# 10-Sensing.net
KiCad netlist of a schematic drawn in Altium Designer
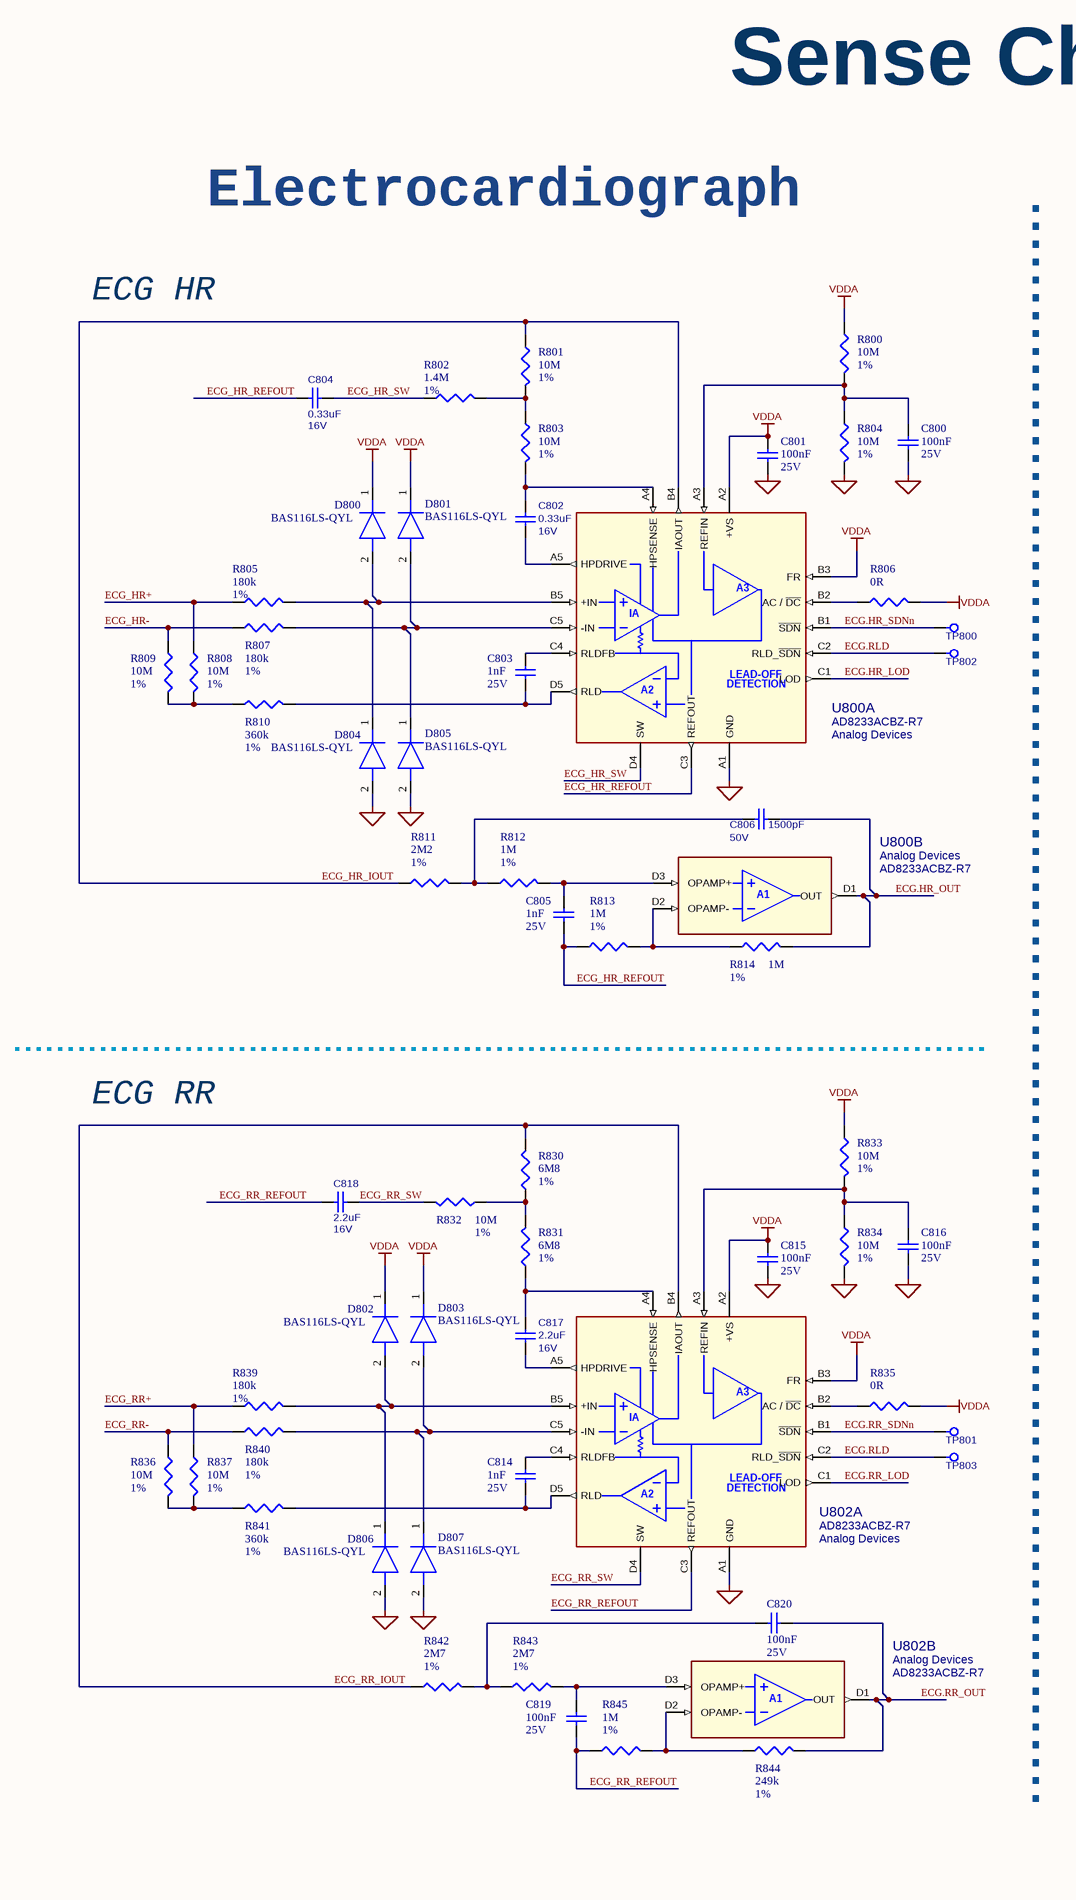
[diagram p0: 10-Sensing.SchDoc, left]
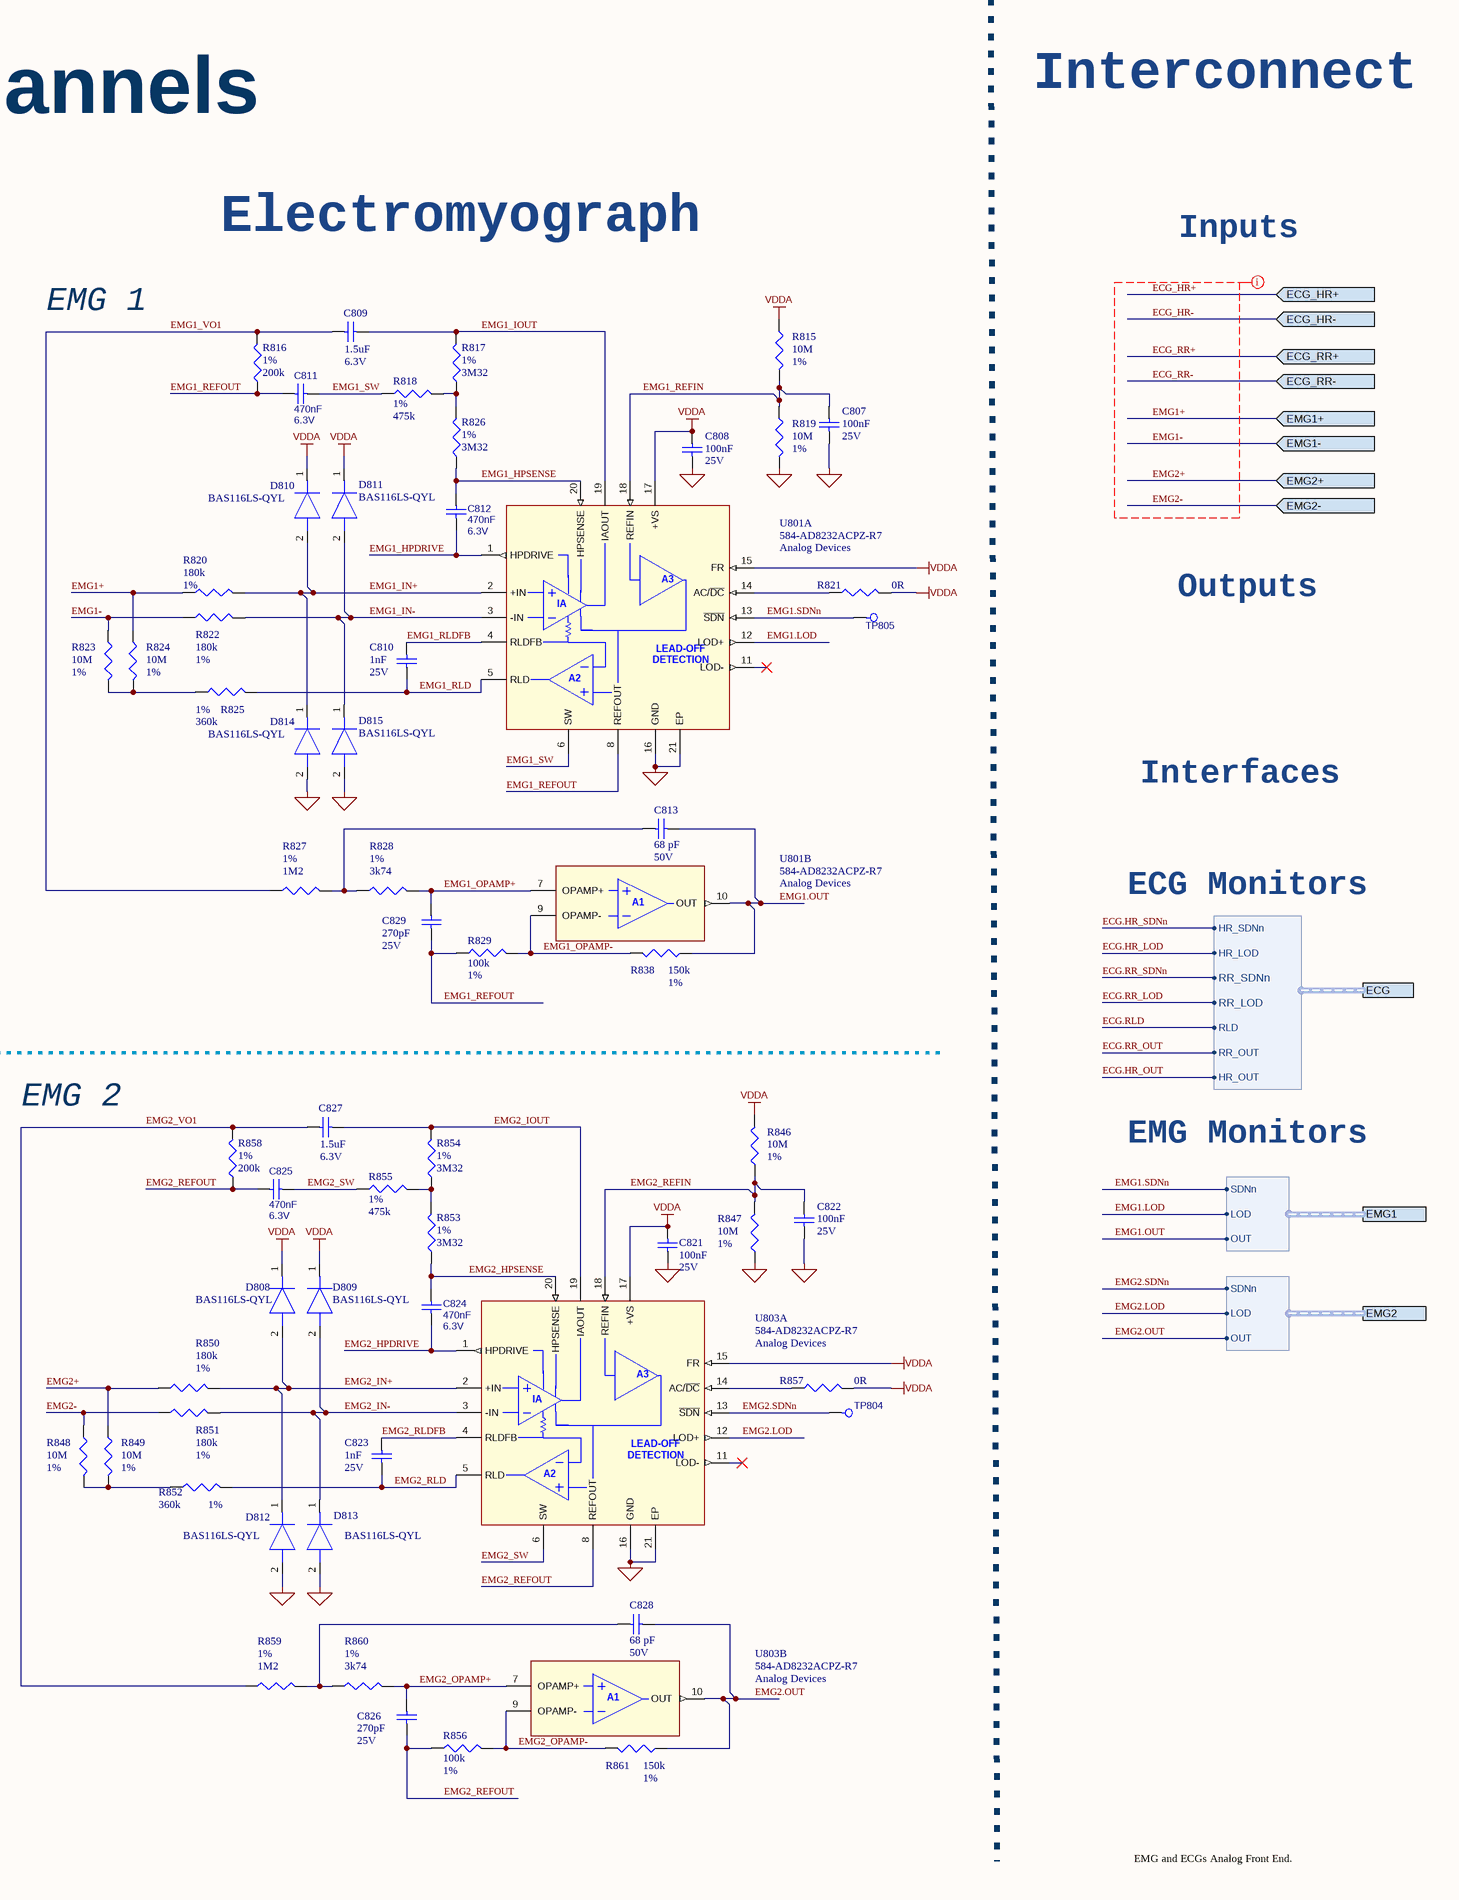
[diagram p1: 10-Sensing.SchDoc, right]

(export (version "E")
  (design (tool "Eeschema 10.0.6"))
  (components
    (comp (ref "C800")
      (value "100nF")
      (footprint "C0201_C")
      (fields
        (field (name "MANUFACTURER") "Murata")
        (field (name "MANUFACTURER PART NUMBER") "GRM033R61E104KE14J")
        (field (name "RATED DC VOLTAGE (URDC)") "25V")
      )
      (libsource (lib "MP-LIBRARY") (part "GRM033R61E104KE14J"))
    )
    (comp (ref "C801")
      (value "100nF")
      (footprint "C0201_C")
      (fields
        (field (name "MANUFACTURER") "Murata")
        (field (name "MANUFACTURER PART NUMBER") "GRM033R61E104KE14J")
        (field (name "RATED DC VOLTAGE (URDC)") "25V")
      )
      (libsource (lib "MP-LIBRARY") (part "GRM033R61E104KE14J"))
    )
    (comp (ref "C802")
      (value "0.33uF")
      (footprint "CAP0402_REDUCED")
      (description "Capacitor, 0.33uF, X7S, 16V, 10%, 0402")
      (fields
        (field (name "MANUFACTURER") "TDK")
        (field (name "RATING") "16V")
        (field (name "MANUFACTURER PART NUMBER") "CGA2B1X7S1C334K050BC")
      )
      (libsource (lib "MP-LIBRARY") (part "CGA2B1X7S1C334K050BC"))
    )
    (comp (ref "C803")
      (value "1nF")
      (footprint "C0201_C")
      (fields
        (field (name "MANUFACTURER") "Murata")
        (field (name "MANUFACTURER PART NUMBER") "GRM033R71E102KA01J")
        (field (name "RATED DC VOLTAGE (URDC)") "25V")
      )
      (libsource (lib "MP-LIBRARY") (part "GRM033R71E102KA01J"))
    )
    (comp (ref "C804")
      (value "0.33uF")
      (footprint "CAP0402_REDUCED")
      (description "Capacitor, 0.33uF, X7S, 16V, 10%, 0402")
      (fields
        (field (name "MANUFACTURER") "TDK")
        (field (name "RATING") "16V")
        (field (name "MANUFACTURER PART NUMBER") "CGA2B1X7S1C334K050BC")
      )
      (libsource (lib "MP-LIBRARY") (part "CGA2B1X7S1C334K050BC"))
    )
    (comp (ref "C805")
      (value "1nF")
      (footprint "C0201_C")
      (fields
        (field (name "MANUFACTURER") "Murata")
        (field (name "MANUFACTURER PART NUMBER") "GRM033R71E102KA01J")
        (field (name "RATED DC VOLTAGE (URDC)") "25V")
      )
      (libsource (lib "MP-LIBRARY") (part "GRM033R71E102KA01J"))
    )
    (comp (ref "C806")
      (value "1500pF")
      (footprint "CAP0402_REDUCED")
      (description "Capacitor, 1500pF, X7R, 50V, 10%, 0402")
      (fields
        (field (name "MANUFACTURER") "Murata")
        (field (name "RATING") "50V")
        (field (name "MANUFACTURER PART NUMBER") "GCM155R71H152KA37D")
      )
      (libsource (lib "MP-LIBRARY") (part "GCM155R71H152KA37D"))
    )
    (comp (ref "C807")
      (value "100nF")
      (footprint "C0201_C")
      (fields
        (field (name "MANUFACTURER") "Murata")
        (field (name "MANUFACTURER PART NUMBER") "GRM033R61E104KE14J")
        (field (name "RATED DC VOLTAGE (URDC)") "25V")
      )
      (libsource (lib "MP-LIBRARY") (part "GRM033R61E104KE14J"))
    )
    (comp (ref "C808")
      (value "100nF")
      (footprint "C0201_C")
      (fields
        (field (name "MANUFACTURER") "Murata")
        (field (name "MANUFACTURER PART NUMBER") "GRM033R61E104KE14J")
        (field (name "RATED DC VOLTAGE (URDC)") "25V")
      )
      (libsource (lib "MP-LIBRARY") (part "GRM033R61E104KE14J"))
    )
    (comp (ref "C809")
      (value "1.5uF")
      (footprint "C0201_C")
      (fields
        (field (name "MANUFACTURER") "Murata")
        (field (name "MANUFACTURER PART NUMBER") "GRM033R60J155ME14D")
        (field (name "RATED DC VOLTAGE (URDC)") "6.3V")
      )
      (libsource (lib "MP-LIBRARY") (part "GRM033R60J155ME14D"))
    )
    (comp (ref "C810")
      (value "1nF")
      (footprint "C0201_C")
      (fields
        (field (name "MANUFACTURER") "Murata")
        (field (name "MANUFACTURER PART NUMBER") "GRM033R71E102KA01J")
        (field (name "RATED DC VOLTAGE (URDC)") "25V")
      )
      (libsource (lib "MP-LIBRARY") (part "GRM033R71E102KA01J"))
    )
    (comp (ref "C811")
      (value "470nF")
      (footprint "C0201_C")
      (description "Capacitor, 470nF, X5R, 6.3V, 10%, 0201, Implant Grade")
      (fields
        (field (name "MANUFACTURER") "Murata")
        (field (name "MANUFACTURER PART NUMBER") "GRT033R60J474KE01D")
        (field (name "RATING") "6.3V")
      )
      (libsource (lib "MP-LIBRARY") (part "GRT033R60J474KE01D"))
    )
    (comp (ref "C812")
      (value "470nF")
      (footprint "C0201_C")
      (description "Capacitor, 470nF, X5R, 6.3V, 10%, 0201, Implant Grade")
      (fields
        (field (name "MANUFACTURER") "Murata")
        (field (name "MANUFACTURER PART NUMBER") "GRT033R60J474KE01D")
        (field (name "RATING") "6.3V")
      )
      (libsource (lib "MP-LIBRARY") (part "GRT033R60J474KE01D"))
    )
    (comp (ref "C813")
      (value "68 pF")
      (footprint "C0201_C")
      (description "68 pF ±5% 50V Ceramic Capacitor C0G, NP0 0201 (0603 Metric)")
      (fields
        (field (name "MANUFACTURER") "Murata Electronics")
        (field (name "MANUFACTURER PART NUMBER") "GRM0335C1H680JA01D")
        (field (name "RATED DC VOLTAGE (URDC)") "50V")
      )
      (libsource (lib "MP-LIBRARY") (part "GRM0335C1H680JA01D"))
    )
    (comp (ref "C814")
      (value "1nF")
      (footprint "C0201_C")
      (fields
        (field (name "MANUFACTURER") "Murata")
        (field (name "MANUFACTURER PART NUMBER") "GRM033R71E102KA01J")
        (field (name "RATED DC VOLTAGE (URDC)") "25V")
      )
      (libsource (lib "MP-LIBRARY") (part "GRM033R71E102KA01J"))
    )
    (comp (ref "C815")
      (value "100nF")
      (footprint "C0201_C")
      (fields
        (field (name "MANUFACTURER") "Murata")
        (field (name "MANUFACTURER PART NUMBER") "GRM033R61E104KE14J")
        (field (name "RATED DC VOLTAGE (URDC)") "25V")
      )
      (libsource (lib "MP-LIBRARY") (part "GRM033R61E104KE14J"))
    )
    (comp (ref "C816")
      (value "100nF")
      (footprint "C0201_C")
      (fields
        (field (name "MANUFACTURER") "Murata")
        (field (name "MANUFACTURER PART NUMBER") "GRM033R61E104KE14J")
        (field (name "RATED DC VOLTAGE (URDC)") "25V")
      )
      (libsource (lib "MP-LIBRARY") (part "GRM033R61E104KE14J"))
    )
    (comp (ref "C817")
      (value "2.2uF")
      (footprint "CAP0603_REDUCED")
      (description "Capacitor, 2.2uF, X7R, 16V, 10%, 0603, Implant-grade")
      (fields
        (field (name "MANUFACTURER") "Murata")
        (field (name "RATING") "16V")
        (field (name "MANUFACTURER PART NUMBER") "GRM188Z71C225ME43J")
      )
      (libsource (lib "MP-LIBRARY") (part "GRM188Z71C225ME43J"))
    )
    (comp (ref "C818")
      (value "2.2uF")
      (footprint "CAP0603_REDUCED")
      (description "Capacitor, 2.2uF, X7R, 16V, 10%, 0603, Implant-grade")
      (fields
        (field (name "MANUFACTURER") "Murata")
        (field (name "RATING") "16V")
        (field (name "MANUFACTURER PART NUMBER") "GRM188Z71C225ME43J")
      )
      (libsource (lib "MP-LIBRARY") (part "GRM188Z71C225ME43J"))
    )
    (comp (ref "C819")
      (value "100nF")
      (footprint "C0201_C")
      (fields
        (field (name "MANUFACTURER") "Murata")
        (field (name "MANUFACTURER PART NUMBER") "GRM033R61E104KE14J")
        (field (name "RATED DC VOLTAGE (URDC)") "25V")
      )
      (libsource (lib "MP-LIBRARY") (part "GRM033R61E104KE14J"))
    )
    (comp (ref "C820")
      (value "100nF")
      (footprint "C0201_C")
      (fields
        (field (name "MANUFACTURER") "Murata")
        (field (name "MANUFACTURER PART NUMBER") "GRM033R61E104KE14J")
        (field (name "RATED DC VOLTAGE (URDC)") "25V")
      )
      (libsource (lib "MP-LIBRARY") (part "GRM033R61E104KE14J"))
    )
    (comp (ref "C821")
      (value "100nF")
      (footprint "C0201_C")
      (fields
        (field (name "MANUFACTURER") "Murata")
        (field (name "MANUFACTURER PART NUMBER") "GRM033R61E104KE14J")
        (field (name "RATED DC VOLTAGE (URDC)") "25V")
      )
      (libsource (lib "MP-LIBRARY") (part "GRM033R61E104KE14J"))
    )
    (comp (ref "C822")
      (value "100nF")
      (footprint "C0201_C")
      (fields
        (field (name "MANUFACTURER") "Murata")
        (field (name "MANUFACTURER PART NUMBER") "GRM033R61E104KE14J")
        (field (name "RATED DC VOLTAGE (URDC)") "25V")
      )
      (libsource (lib "MP-LIBRARY") (part "GRM033R61E104KE14J"))
    )
    (comp (ref "C823")
      (value "1nF")
      (footprint "C0201_C")
      (fields
        (field (name "MANUFACTURER") "Murata")
        (field (name "MANUFACTURER PART NUMBER") "GRM033R71E102KA01J")
        (field (name "RATED DC VOLTAGE (URDC)") "25V")
      )
      (libsource (lib "MP-LIBRARY") (part "GRM033R71E102KA01J"))
    )
    (comp (ref "C824")
      (value "470nF")
      (footprint "C0201_C")
      (description "Capacitor, 470nF, X5R, 6.3V, 10%, 0201, Implant Grade")
      (fields
        (field (name "MANUFACTURER") "Murata")
        (field (name "MANUFACTURER PART NUMBER") "GRT033R60J474KE01D")
        (field (name "RATING") "6.3V")
      )
      (libsource (lib "MP-LIBRARY") (part "GRT033R60J474KE01D"))
    )
    (comp (ref "C825")
      (value "470nF")
      (footprint "C0201_C")
      (description "Capacitor, 470nF, X5R, 6.3V, 10%, 0201, Implant Grade")
      (fields
        (field (name "MANUFACTURER") "Murata")
        (field (name "MANUFACTURER PART NUMBER") "GRT033R60J474KE01D")
        (field (name "RATING") "6.3V")
      )
      (libsource (lib "MP-LIBRARY") (part "GRT033R60J474KE01D"))
    )
    (comp (ref "C826")
      (value "270pF")
      (footprint "C0201_C")
      (description "270 pF ±5% 25V Ceramic Capacitor C0G, NP0 0201 (0603 Metric)")
      (fields
        (field (name "MANUFACTURER") "Murata Electronics")
        (field (name "MANUFACTURER PART NUMBER") "GRM0335C1E271JA01D")
        (field (name "RATED DC VOLTAGE (URDC)") "25V")
      )
      (libsource (lib "MP-LIBRARY") (part "GRM0335C1E271JA01D"))
    )
    (comp (ref "C827")
      (value "1.5uF")
      (footprint "C0201_C")
      (fields
        (field (name "MANUFACTURER") "Murata")
        (field (name "MANUFACTURER PART NUMBER") "GRM033R60J155ME14D")
        (field (name "RATED DC VOLTAGE (URDC)") "6.3V")
      )
      (libsource (lib "MP-LIBRARY") (part "GRM033R60J155ME14D"))
    )
    (comp (ref "C828")
      (value "68 pF")
      (footprint "C0201_C")
      (description "68 pF ±5% 50V Ceramic Capacitor C0G, NP0 0201 (0603 Metric)")
      (fields
        (field (name "MANUFACTURER") "Murata Electronics")
        (field (name "MANUFACTURER PART NUMBER") "GRM0335C1H680JA01D")
        (field (name "RATED DC VOLTAGE (URDC)") "50V")
      )
      (libsource (lib "MP-LIBRARY") (part "GRM0335C1H680JA01D"))
    )
    (comp (ref "C829")
      (value "270pF")
      (footprint "C0201_C")
      (description "270 pF ±5% 25V Ceramic Capacitor C0G, NP0 0201 (0603 Metric)")
      (fields
        (field (name "MANUFACTURER") "Murata Electronics")
        (field (name "MANUFACTURER PART NUMBER") "GRM0335C1E271JA01D")
        (field (name "RATED DC VOLTAGE (URDC)") "25V")
      )
      (libsource (lib "MP-LIBRARY") (part "GRM0335C1E271JA01D"))
    )
    (comp (ref "D800")
      (value "BAS116LS-QYL")
      (footprint "BAS116LSQYL")
      (description "Diode")
      (fields (field (name "MOUSER PART NUMBER") "771-BAS116LS-QYL") (field (name "MANUFACTURER") "Nexperia"))
      (libsource (lib "MP-LIBRARY") (part "BAS116LS-QYL"))
    )
    (comp (ref "D801")
      (value "BAS116LS-QYL")
      (footprint "BAS116LSQYL")
      (description "Diode")
      (fields (field (name "MOUSER PART NUMBER") "771-BAS116LS-QYL") (field (name "MANUFACTURER") "Nexperia"))
      (libsource (lib "MP-LIBRARY") (part "BAS116LS-QYL"))
    )
    (comp (ref "D802")
      (value "BAS116LS-QYL")
      (footprint "BAS116LSQYL")
      (description "Diode")
      (fields (field (name "MOUSER PART NUMBER") "771-BAS116LS-QYL") (field (name "MANUFACTURER") "Nexperia"))
      (libsource (lib "MP-LIBRARY") (part "BAS116LS-QYL"))
    )
    (comp (ref "D803")
      (value "BAS116LS-QYL")
      (footprint "BAS116LSQYL")
      (description "Diode")
      (fields (field (name "MOUSER PART NUMBER") "771-BAS116LS-QYL") (field (name "MANUFACTURER") "Nexperia"))
      (libsource (lib "MP-LIBRARY") (part "BAS116LS-QYL"))
    )
    (comp (ref "D804")
      (value "BAS116LS-QYL")
      (footprint "BAS116LSQYL")
      (description "Diode")
      (fields (field (name "MOUSER PART NUMBER") "771-BAS116LS-QYL") (field (name "MANUFACTURER") "Nexperia"))
      (libsource (lib "MP-LIBRARY") (part "BAS116LS-QYL"))
    )
    (comp (ref "D805")
      (value "BAS116LS-QYL")
      (footprint "BAS116LSQYL")
      (description "Diode")
      (fields (field (name "MOUSER PART NUMBER") "771-BAS116LS-QYL") (field (name "MANUFACTURER") "Nexperia"))
      (libsource (lib "MP-LIBRARY") (part "BAS116LS-QYL"))
    )
    (comp (ref "D806")
      (value "BAS116LS-QYL")
      (footprint "BAS116LSQYL")
      (description "Diode")
      (fields (field (name "MOUSER PART NUMBER") "771-BAS116LS-QYL") (field (name "MANUFACTURER") "Nexperia"))
      (libsource (lib "MP-LIBRARY") (part "BAS116LS-QYL"))
    )
    (comp (ref "D807")
      (value "BAS116LS-QYL")
      (footprint "BAS116LSQYL")
      (description "Diode")
      (fields (field (name "MOUSER PART NUMBER") "771-BAS116LS-QYL") (field (name "MANUFACTURER") "Nexperia"))
      (libsource (lib "MP-LIBRARY") (part "BAS116LS-QYL"))
    )
    (comp (ref "D808")
      (value "BAS116LS-QYL")
      (footprint "BAS116LSQYL")
      (description "Diode")
      (fields (field (name "MOUSER PART NUMBER") "771-BAS116LS-QYL") (field (name "MANUFACTURER") "Nexperia"))
      (libsource (lib "MP-LIBRARY") (part "BAS116LS-QYL"))
    )
    (comp (ref "D809")
      (value "BAS116LS-QYL")
      (footprint "BAS116LSQYL")
      (description "Diode")
      (fields (field (name "MOUSER PART NUMBER") "771-BAS116LS-QYL") (field (name "MANUFACTURER") "Nexperia"))
      (libsource (lib "MP-LIBRARY") (part "BAS116LS-QYL"))
    )
    (comp (ref "D810")
      (value "BAS116LS-QYL")
      (footprint "BAS116LSQYL")
      (description "Diode")
      (fields (field (name "MOUSER PART NUMBER") "771-BAS116LS-QYL") (field (name "MANUFACTURER") "Nexperia"))
      (libsource (lib "MP-LIBRARY") (part "BAS116LS-QYL"))
    )
    (comp (ref "D811")
      (value "BAS116LS-QYL")
      (footprint "BAS116LSQYL")
      (description "Diode")
      (fields (field (name "MOUSER PART NUMBER") "771-BAS116LS-QYL") (field (name "MANUFACTURER") "Nexperia"))
      (libsource (lib "MP-LIBRARY") (part "BAS116LS-QYL"))
    )
    (comp (ref "D812")
      (value "BAS116LS-QYL")
      (footprint "BAS116LSQYL")
      (description "Diode")
      (fields (field (name "MOUSER PART NUMBER") "771-BAS116LS-QYL") (field (name "MANUFACTURER") "Nexperia"))
      (libsource (lib "MP-LIBRARY") (part "BAS116LS-QYL"))
    )
    (comp (ref "D813")
      (value "BAS116LS-QYL")
      (footprint "BAS116LSQYL")
      (description "Diode")
      (fields (field (name "MOUSER PART NUMBER") "771-BAS116LS-QYL") (field (name "MANUFACTURER") "Nexperia"))
      (libsource (lib "MP-LIBRARY") (part "BAS116LS-QYL"))
    )
    (comp (ref "D814")
      (value "BAS116LS-QYL")
      (footprint "BAS116LSQYL")
      (description "Diode")
      (fields (field (name "MOUSER PART NUMBER") "771-BAS116LS-QYL") (field (name "MANUFACTURER") "Nexperia"))
      (libsource (lib "MP-LIBRARY") (part "BAS116LS-QYL"))
    )
    (comp (ref "D815")
      (value "BAS116LS-QYL")
      (footprint "BAS116LSQYL")
      (description "Diode")
      (fields (field (name "MOUSER PART NUMBER") "771-BAS116LS-QYL") (field (name "MANUFACTURER") "Nexperia"))
      (libsource (lib "MP-LIBRARY") (part "BAS116LS-QYL"))
    )
    (comp (ref "R800")
      (value "10M")
      (footprint "R0201_C")
      (fields
        (field (name "MANUFACTURER") "Vishay Draloric")
        (field (name "MANUFACTURER PART NUMBER") "CRCW020110M0FNED")
        (field (name "TOLERANCE") "1%")
        (field (name "POWER") "50mW")
      )
      (libsource (lib "MP-LIBRARY") (part "CRCW020110M0FNED"))
    )
    (comp (ref "R801")
      (value "10M")
      (footprint "R0201_C")
      (fields
        (field (name "MANUFACTURER") "Vishay Draloric")
        (field (name "MANUFACTURER PART NUMBER") "CRCW020110M0FNED")
        (field (name "TOLERANCE") "1%")
        (field (name "POWER") "50mW")
      )
      (libsource (lib "MP-LIBRARY") (part "CRCW020110M0FNED"))
    )
    (comp (ref "R802")
      (value "1.4M")
      (footprint "R0201_C")
      (fields
        (field (name "MANUFACTURER") "Vishay Draloric")
        (field (name "MANUFACTURER PART NUMBER") "CRCW02011M40FNED")
        (field (name "TOLERANCE") "1%")
        (field (name "POWER") "50mW")
      )
      (libsource (lib "MP-LIBRARY") (part "CRCW02011M40FNED"))
    )
    (comp (ref "R803")
      (value "10M")
      (footprint "R0201_C")
      (fields
        (field (name "MANUFACTURER") "Vishay Draloric")
        (field (name "MANUFACTURER PART NUMBER") "CRCW020110M0FNED")
        (field (name "TOLERANCE") "1%")
        (field (name "POWER") "50mW")
      )
      (libsource (lib "MP-LIBRARY") (part "CRCW020110M0FNED"))
    )
    (comp (ref "R804")
      (value "10M")
      (footprint "R0201_C")
      (fields
        (field (name "MANUFACTURER") "Vishay Draloric")
        (field (name "MANUFACTURER PART NUMBER") "CRCW020110M0FNED")
        (field (name "TOLERANCE") "1%")
        (field (name "POWER") "50mW")
      )
      (libsource (lib "MP-LIBRARY") (part "CRCW020110M0FNED"))
    )
    (comp (ref "R805")
      (value "180k")
      (footprint "R0201_C")
      (fields
        (field (name "MANUFACTURER") "Vishay")
        (field (name "MANUFACTURER PART NUMBER") "CRCW0201180KFNED")
        (field (name "TOLERANCE") "1%")
        (field (name "POWER") "50mW")
      )
      (libsource (lib "MP-LIBRARY") (part "CRCW0201180KFNED"))
    )
    (comp (ref "R806")
      (value "0R")
      (footprint "R0201_C")
      (description "Fixed Resistor, Metal Glaze/thick Film, 0.05W, 0ohm, Surface Mount, 0201")
      (fields
        (field (name "MANUFACTURER") "Vishay")
        (field (name "MANUFACTURER PART NUMBER") "CRCW02010000Z0ED")
      )
      (libsource (lib "MP-LIBRARY") (part "CRCW02010000Z0ED"))
    )
    (comp (ref "R807")
      (value "180k")
      (footprint "R0201_C")
      (fields
        (field (name "MANUFACTURER") "Vishay")
        (field (name "MANUFACTURER PART NUMBER") "CRCW0201180KFNED")
        (field (name "TOLERANCE") "1%")
        (field (name "POWER") "50mW")
      )
      (libsource (lib "MP-LIBRARY") (part "CRCW0201180KFNED"))
    )
    (comp (ref "R808")
      (value "10M")
      (footprint "R0201_C")
      (fields
        (field (name "MANUFACTURER") "Vishay Draloric")
        (field (name "MANUFACTURER PART NUMBER") "CRCW020110M0FNED")
        (field (name "TOLERANCE") "1%")
        (field (name "POWER") "50mW")
      )
      (libsource (lib "MP-LIBRARY") (part "CRCW020110M0FNED"))
    )
    (comp (ref "R809")
      (value "10M")
      (footprint "R0201_C")
      (fields
        (field (name "MANUFACTURER") "Vishay Draloric")
        (field (name "MANUFACTURER PART NUMBER") "CRCW020110M0FNED")
        (field (name "TOLERANCE") "1%")
        (field (name "POWER") "50mW")
      )
      (libsource (lib "MP-LIBRARY") (part "CRCW020110M0FNED"))
    )
    (comp (ref "R810")
      (value "360k")
      (footprint "R0201_C")
      (fields
        (field (name "MANUFACTURER") "Vishay")
        (field (name "MANUFACTURER PART NUMBER") "CRCW0201360KFNED")
        (field (name "TOLERANCE") "1%")
        (field (name "POWER") "50mW")
      )
      (libsource (lib "MP-LIBRARY") (part "CRCW0201360KFNED"))
    )
    (comp (ref "R811")
      (value "2M2")
      (footprint "R0201_C")
      (fields
        (field (name "MANUFACTURER") "Vishay Draloric")
        (field (name "MANUFACTURER PART NUMBER") "CRCW02012M20FNED")
        (field (name "TOLERANCE") "1%")
        (field (name "POWER") "50mW")
      )
      (libsource (lib "MP-LIBRARY") (part "CRCW02012M20FNED"))
    )
    (comp (ref "R812")
      (value "1M")
      (footprint "R0201_C")
      (fields
        (field (name "MANUFACTURER") "Vishay")
        (field (name "MANUFACTURER PART NUMBER") "CRCW02011M00FNED")
        (field (name "TOLERANCE") "1%")
        (field (name "POWER") "50mW")
      )
      (libsource (lib "MP-LIBRARY") (part "CRCW02011M00FNED"))
    )
    (comp (ref "R813")
      (value "1M")
      (footprint "R0201_C")
      (fields
        (field (name "MANUFACTURER") "Vishay")
        (field (name "MANUFACTURER PART NUMBER") "CRCW02011M00FNED")
        (field (name "TOLERANCE") "1%")
        (field (name "POWER") "50mW")
      )
      (libsource (lib "MP-LIBRARY") (part "CRCW02011M00FNED"))
    )
    (comp (ref "R814")
      (value "1M")
      (footprint "R0201_C")
      (fields
        (field (name "MANUFACTURER") "Vishay")
        (field (name "MANUFACTURER PART NUMBER") "CRCW02011M00FNED")
        (field (name "TOLERANCE") "1%")
        (field (name "POWER") "50mW")
      )
      (libsource (lib "MP-LIBRARY") (part "CRCW02011M00FNED"))
    )
    (comp (ref "R815")
      (value "10M")
      (footprint "R0201_C")
      (fields
        (field (name "MANUFACTURER") "Vishay Draloric")
        (field (name "MANUFACTURER PART NUMBER") "CRCW020110M0FNED")
        (field (name "TOLERANCE") "1%")
        (field (name "POWER") "50mW")
      )
      (libsource (lib "MP-LIBRARY") (part "CRCW020110M0FNED"))
    )
    (comp (ref "R816")
      (value "200k")
      (footprint "R0201_C")
      (fields
        (field (name "MANUFACTURER") "Vishay")
        (field (name "MANUFACTURER PART NUMBER") "CRCW0201200KFNED")
        (field (name "TOLERANCE") "1%")
        (field (name "POWER") "50mW")
      )
      (libsource (lib "MP-LIBRARY") (part "CRCW0201200KFNED"))
    )
    (comp (ref "R817")
      (value "3M32")
      (footprint "R0201_C")
      (description "3.32 MOhms ±1% 0.05W, 1/20W Chip Resistor 0201 (0603 Metric) Thick Film")
      (fields
        (field (name "MANUFACTURER") "Vishay Dale")
        (field (name "MANUFACTURER PART NUMBER") "CRCW02013M32FNED")
        (field (name "TOLERANCE") "1%")
      )
      (libsource (lib "MP-LIBRARY") (part "CRCW02013M32FNED"))
    )
    (comp (ref "R818")
      (value "475k")
      (footprint "R0201_C")
      (description "475 kOhms ±1% 0.05W, 1/20W Chip Resistor 0201 (0603 Metric) Thick Film")
      (fields
        (field (name "MANUFACTURER") "Vishay Dale")
        (field (name "MANUFACTURER PART NUMBER") "CRCW0201475KFNED")
        (field (name "TOLERANCE") "1%")
      )
      (libsource (lib "MP-LIBRARY") (part "CRCW0201475KFNED"))
    )
    (comp (ref "R819")
      (value "10M")
      (footprint "R0201_C")
      (fields
        (field (name "MANUFACTURER") "Vishay Draloric")
        (field (name "MANUFACTURER PART NUMBER") "CRCW020110M0FNED")
        (field (name "TOLERANCE") "1%")
        (field (name "POWER") "50mW")
      )
      (libsource (lib "MP-LIBRARY") (part "CRCW020110M0FNED"))
    )
    (comp (ref "R820")
      (value "180k")
      (footprint "R0201_C")
      (fields
        (field (name "MANUFACTURER") "Vishay")
        (field (name "MANUFACTURER PART NUMBER") "CRCW0201180KFNED")
        (field (name "TOLERANCE") "1%")
        (field (name "POWER") "50mW")
      )
      (libsource (lib "MP-LIBRARY") (part "CRCW0201180KFNED"))
    )
    (comp (ref "R821")
      (value "0R")
      (footprint "R0201_C")
      (description "Fixed Resistor, Metal Glaze/thick Film, 0.05W, 0ohm, Surface Mount, 0201")
      (fields
        (field (name "MANUFACTURER") "Vishay")
        (field (name "MANUFACTURER PART NUMBER") "CRCW02010000Z0ED")
      )
      (libsource (lib "MP-LIBRARY") (part "CRCW02010000Z0ED"))
    )
    (comp (ref "R822")
      (value "180k")
      (footprint "R0201_C")
      (fields
        (field (name "MANUFACTURER") "Vishay")
        (field (name "MANUFACTURER PART NUMBER") "CRCW0201180KFNED")
        (field (name "TOLERANCE") "1%")
        (field (name "POWER") "50mW")
      )
      (libsource (lib "MP-LIBRARY") (part "CRCW0201180KFNED"))
    )
    (comp (ref "R823")
      (value "10M")
      (footprint "R0201_C")
      (fields
        (field (name "MANUFACTURER") "Vishay Draloric")
        (field (name "MANUFACTURER PART NUMBER") "CRCW020110M0FNED")
        (field (name "TOLERANCE") "1%")
        (field (name "POWER") "50mW")
      )
      (libsource (lib "MP-LIBRARY") (part "CRCW020110M0FNED"))
    )
    (comp (ref "R824")
      (value "10M")
      (footprint "R0201_C")
      (fields
        (field (name "MANUFACTURER") "Vishay Draloric")
        (field (name "MANUFACTURER PART NUMBER") "CRCW020110M0FNED")
        (field (name "TOLERANCE") "1%")
        (field (name "POWER") "50mW")
      )
      (libsource (lib "MP-LIBRARY") (part "CRCW020110M0FNED"))
    )
    (comp (ref "R825")
      (value "360k")
      (footprint "R0201_C")
      (fields
        (field (name "MANUFACTURER") "Vishay")
        (field (name "MANUFACTURER PART NUMBER") "CRCW0201360KFNED")
        (field (name "TOLERANCE") "1%")
        (field (name "POWER") "50mW")
      )
      (libsource (lib "MP-LIBRARY") (part "CRCW0201360KFNED"))
    )
    (comp (ref "R826")
      (value "3M32")
      (footprint "R0201_C")
      (description "3.32 MOhms ±1% 0.05W, 1/20W Chip Resistor 0201 (0603 Metric) Thick Film")
      (fields
        (field (name "MANUFACTURER") "Vishay Dale")
        (field (name "MANUFACTURER PART NUMBER") "CRCW02013M32FNED")
        (field (name "TOLERANCE") "1%")
      )
      (libsource (lib "MP-LIBRARY") (part "CRCW02013M32FNED"))
    )
    (comp (ref "R827")
      (value "1M2")
      (footprint "R0201_C")
      (description "1.2 MOhms ±1% 0.05W, 1/20W Chip Resistor 0201 (0603 Metric) Thick Film")
      (fields
        (field (name "MANUFACTURER") "Vishay Dale")
        (field (name "MANUFACTURER PART NUMBER") "CRCW02011M20FNED")
        (field (name "TOLERANCE") "1%")
      )
      (libsource (lib "MP-LIBRARY") (part "CRCW02011M20FNED"))
    )
    (comp (ref "R828")
      (value "3k74")
      (footprint "R0201_C")
      (description "3.74 kOhms ±1% 0.05W, 1/20W Chip Resistor 0201 (0603 Metric) Thick Film")
      (fields
        (field (name "MANUFACTURER") "Vishay Dale")
        (field (name "MANUFACTURER PART NUMBER") "CRCW02013K74FNED")
        (field (name "TOLERANCE") "1%")
      )
      (libsource (lib "MP-LIBRARY") (part "CRCW02013K74FNED"))
    )
    (comp (ref "R829")
      (value "100k")
      (footprint "R0201_C")
      (fields
        (field (name "MANUFACTURER") "Vishay")
        (field (name "MANUFACTURER PART NUMBER") "CRCW0201100KFNED")
        (field (name "TOLERANCE") "1%")
        (field (name "POWER") "50mW")
      )
      (libsource (lib "MP-LIBRARY") (part "CRCW0201100KFNED"))
    )
    (comp (ref "R830")
      (value "6M8")
      (footprint "R0201_C")
      (fields
        (field (name "MANUFACTURER") "Vishay Draloric")
        (field (name "MANUFACTURER PART NUMBER") "CRCW02016M80FNED")
        (field (name "TOLERANCE") "1%")
        (field (name "POWER") "50mW")
      )
      (libsource (lib "MP-LIBRARY") (part "CRCW02016M80FNED"))
    )
    (comp (ref "R831")
      (value "6M8")
      (footprint "R0201_C")
      (fields
        (field (name "MANUFACTURER") "Vishay Draloric")
        (field (name "MANUFACTURER PART NUMBER") "CRCW02016M80FNED")
        (field (name "TOLERANCE") "1%")
        (field (name "POWER") "50mW")
      )
      (libsource (lib "MP-LIBRARY") (part "CRCW02016M80FNED"))
    )
    (comp (ref "R832")
      (value "10M")
      (footprint "R0201_C")
      (fields
        (field (name "MANUFACTURER") "Vishay Draloric")
        (field (name "MANUFACTURER PART NUMBER") "CRCW020110M0FNED")
        (field (name "TOLERANCE") "1%")
        (field (name "POWER") "50mW")
      )
      (libsource (lib "MP-LIBRARY") (part "CRCW020110M0FNED"))
    )
    (comp (ref "R833")
      (value "10M")
      (footprint "R0201_C")
      (fields
        (field (name "MANUFACTURER") "Vishay Draloric")
        (field (name "MANUFACTURER PART NUMBER") "CRCW020110M0FNED")
        (field (name "TOLERANCE") "1%")
        (field (name "POWER") "50mW")
      )
      (libsource (lib "MP-LIBRARY") (part "CRCW020110M0FNED"))
    )
    (comp (ref "R834")
      (value "10M")
      (footprint "R0201_C")
      (fields
        (field (name "MANUFACTURER") "Vishay Draloric")
        (field (name "MANUFACTURER PART NUMBER") "CRCW020110M0FNED")
        (field (name "TOLERANCE") "1%")
        (field (name "POWER") "50mW")
      )
      (libsource (lib "MP-LIBRARY") (part "CRCW020110M0FNED"))
    )
    (comp (ref "R835")
      (value "0R")
      (footprint "R0201_C")
      (description "Fixed Resistor, Metal Glaze/thick Film, 0.05W, 0ohm, Surface Mount, 0201")
      (fields
        (field (name "MANUFACTURER") "Vishay")
        (field (name "MANUFACTURER PART NUMBER") "CRCW02010000Z0ED")
      )
      (libsource (lib "MP-LIBRARY") (part "CRCW02010000Z0ED"))
    )
    (comp (ref "R836")
      (value "10M")
      (footprint "R0201_C")
      (fields
        (field (name "MANUFACTURER") "Vishay Draloric")
        (field (name "MANUFACTURER PART NUMBER") "CRCW020110M0FNED")
        (field (name "TOLERANCE") "1%")
        (field (name "POWER") "50mW")
      )
      (libsource (lib "MP-LIBRARY") (part "CRCW020110M0FNED"))
    )
    (comp (ref "R837")
      (value "10M")
      (footprint "R0201_C")
      (fields
        (field (name "MANUFACTURER") "Vishay Draloric")
        (field (name "MANUFACTURER PART NUMBER") "CRCW020110M0FNED")
        (field (name "TOLERANCE") "1%")
        (field (name "POWER") "50mW")
      )
      (libsource (lib "MP-LIBRARY") (part "CRCW020110M0FNED"))
    )
    (comp (ref "R838")
      (value "150k")
      (footprint "R0201_C")
      (fields
        (field (name "MANUFACTURER") "Vishay")
        (field (name "MANUFACTURER PART NUMBER") "CRCW0201150KFNED")
        (field (name "TOLERANCE") "1%")
        (field (name "POWER") "50mW")
      )
      (libsource (lib "MP-LIBRARY") (part "CRCW0201150KFNED"))
    )
    (comp (ref "R839")
      (value "180k")
      (footprint "R0201_C")
      (fields
        (field (name "MANUFACTURER") "Vishay")
        (field (name "MANUFACTURER PART NUMBER") "CRCW0201180KFNED")
        (field (name "TOLERANCE") "1%")
        (field (name "POWER") "50mW")
      )
      (libsource (lib "MP-LIBRARY") (part "CRCW0201180KFNED"))
    )
    (comp (ref "R840")
      (value "180k")
      (footprint "R0201_C")
      (fields
        (field (name "MANUFACTURER") "Vishay")
        (field (name "MANUFACTURER PART NUMBER") "CRCW0201180KFNED")
        (field (name "TOLERANCE") "1%")
        (field (name "POWER") "50mW")
      )
      (libsource (lib "MP-LIBRARY") (part "CRCW0201180KFNED"))
    )
    (comp (ref "R841")
      (value "360k")
      (footprint "R0201_C")
      (fields
        (field (name "MANUFACTURER") "Vishay")
        (field (name "MANUFACTURER PART NUMBER") "CRCW0201360KFNED")
        (field (name "TOLERANCE") "1%")
        (field (name "POWER") "50mW")
      )
      (libsource (lib "MP-LIBRARY") (part "CRCW0201360KFNED"))
    )
    (comp (ref "R842")
      (value "2M7")
      (footprint "R0201_C")
      (fields
        (field (name "MANUFACTURER") "Vishay Draloric")
        (field (name "MANUFACTURER PART NUMBER") "CRCW02012M70FNED")
        (field (name "TOLERANCE") "1%")
        (field (name "POWER") "50mW")
      )
      (libsource (lib "MP-LIBRARY") (part "CRCW02012M70FNED"))
    )
    (comp (ref "R843")
      (value "2M7")
      (footprint "R0201_C")
      (fields
        (field (name "MANUFACTURER") "Vishay Draloric")
        (field (name "MANUFACTURER PART NUMBER") "CRCW02012M70FNED")
        (field (name "TOLERANCE") "1%")
        (field (name "POWER") "50mW")
      )
      (libsource (lib "MP-LIBRARY") (part "CRCW02012M70FNED"))
    )
    (comp (ref "R844")
      (value "249k")
      (footprint "R0201_C")
      (fields
        (field (name "MANUFACTURER") "Vishay")
        (field (name "MANUFACTURER PART NUMBER") "CRCW0201249KFNED")
        (field (name "TOLERANCE") "1%")
        (field (name "POWER") "50mW")
      )
      (libsource (lib "MP-LIBRARY") (part "CRCW0201249KFNED"))
    )
    (comp (ref "R845")
      (value "1M")
      (footprint "R0201_C")
      (fields
        (field (name "MANUFACTURER") "Vishay")
        (field (name "MANUFACTURER PART NUMBER") "CRCW02011M00FNED")
        (field (name "TOLERANCE") "1%")
        (field (name "POWER") "50mW")
      )
      (libsource (lib "MP-LIBRARY") (part "CRCW02011M00FNED"))
    )
    (comp (ref "R846")
      (value "10M")
      (footprint "R0201_C")
      (fields
        (field (name "MANUFACTURER") "Vishay Draloric")
        (field (name "MANUFACTURER PART NUMBER") "CRCW020110M0FNED")
        (field (name "TOLERANCE") "1%")
        (field (name "POWER") "50mW")
      )
      (libsource (lib "MP-LIBRARY") (part "CRCW020110M0FNED"))
    )
    (comp (ref "R847")
      (value "10M")
      (footprint "R0201_C")
      (fields
        (field (name "MANUFACTURER") "Vishay Draloric")
        (field (name "MANUFACTURER PART NUMBER") "CRCW020110M0FNED")
        (field (name "TOLERANCE") "1%")
        (field (name "POWER") "50mW")
      )
      (libsource (lib "MP-LIBRARY") (part "CRCW020110M0FNED"))
    )
    (comp (ref "R848")
      (value "10M")
      (footprint "R0201_C")
      (fields
        (field (name "MANUFACTURER") "Vishay Draloric")
        (field (name "MANUFACTURER PART NUMBER") "CRCW020110M0FNED")
        (field (name "TOLERANCE") "1%")
        (field (name "POWER") "50mW")
      )
      (libsource (lib "MP-LIBRARY") (part "CRCW020110M0FNED"))
    )
    (comp (ref "R849")
      (value "10M")
      (footprint "R0201_C")
      (fields
        (field (name "MANUFACTURER") "Vishay Draloric")
        (field (name "MANUFACTURER PART NUMBER") "CRCW020110M0FNED")
        (field (name "TOLERANCE") "1%")
        (field (name "POWER") "50mW")
      )
      (libsource (lib "MP-LIBRARY") (part "CRCW020110M0FNED"))
    )
    (comp (ref "R850")
      (value "180k")
      (footprint "R0201_C")
      (fields
        (field (name "MANUFACTURER") "Vishay")
        (field (name "MANUFACTURER PART NUMBER") "CRCW0201180KFNED")
        (field (name "TOLERANCE") "1%")
        (field (name "POWER") "50mW")
      )
      (libsource (lib "MP-LIBRARY") (part "CRCW0201180KFNED"))
    )
    (comp (ref "R851")
      (value "180k")
      (footprint "R0201_C")
      (fields
        (field (name "MANUFACTURER") "Vishay")
        (field (name "MANUFACTURER PART NUMBER") "CRCW0201180KFNED")
        (field (name "TOLERANCE") "1%")
        (field (name "POWER") "50mW")
      )
      (libsource (lib "MP-LIBRARY") (part "CRCW0201180KFNED"))
    )
    (comp (ref "R852")
      (value "360k")
      (footprint "R0201_C")
      (fields
        (field (name "MANUFACTURER") "Vishay")
        (field (name "MANUFACTURER PART NUMBER") "CRCW0201360KFNED")
        (field (name "TOLERANCE") "1%")
        (field (name "POWER") "50mW")
      )
      (libsource (lib "MP-LIBRARY") (part "CRCW0201360KFNED"))
    )
    (comp (ref "R853")
      (value "3M32")
      (footprint "R0201_C")
      (description "3.32 MOhms ±1% 0.05W, 1/20W Chip Resistor 0201 (0603 Metric) Thick Film")
      (fields
        (field (name "MANUFACTURER") "Vishay Dale")
        (field (name "MANUFACTURER PART NUMBER") "CRCW02013M32FNED")
        (field (name "TOLERANCE") "1%")
      )
      (libsource (lib "MP-LIBRARY") (part "CRCW02013M32FNED"))
    )
    (comp (ref "R854")
      (value "3M32")
      (footprint "R0201_C")
      (description "3.32 MOhms ±1% 0.05W, 1/20W Chip Resistor 0201 (0603 Metric) Thick Film")
      (fields
        (field (name "MANUFACTURER") "Vishay Dale")
        (field (name "MANUFACTURER PART NUMBER") "CRCW02013M32FNED")
        (field (name "TOLERANCE") "1%")
      )
      (libsource (lib "MP-LIBRARY") (part "CRCW02013M32FNED"))
    )
    (comp (ref "R855")
      (value "475k")
      (footprint "R0201_C")
      (description "475 kOhms ±1% 0.05W, 1/20W Chip Resistor 0201 (0603 Metric) Thick Film")
      (fields
        (field (name "MANUFACTURER") "Vishay Dale")
        (field (name "MANUFACTURER PART NUMBER") "CRCW0201475KFNED")
        (field (name "TOLERANCE") "1%")
      )
      (libsource (lib "MP-LIBRARY") (part "CRCW0201475KFNED"))
    )
    (comp (ref "R856")
      (value "100k")
      (footprint "R0201_C")
      (fields
        (field (name "MANUFACTURER") "Vishay")
        (field (name "MANUFACTURER PART NUMBER") "CRCW0201100KFNED")
        (field (name "TOLERANCE") "1%")
        (field (name "POWER") "50mW")
      )
      (libsource (lib "MP-LIBRARY") (part "CRCW0201100KFNED"))
    )
    (comp (ref "R857")
      (value "0R")
      (footprint "R0201_C")
      (description "Fixed Resistor, Metal Glaze/thick Film, 0.05W, 0ohm, Surface Mount, 0201")
      (fields
        (field (name "MANUFACTURER") "Vishay")
        (field (name "MANUFACTURER PART NUMBER") "CRCW02010000Z0ED")
      )
      (libsource (lib "MP-LIBRARY") (part "CRCW02010000Z0ED"))
    )
    (comp (ref "R858")
      (value "200k")
      (footprint "R0201_C")
      (fields
        (field (name "MANUFACTURER") "Vishay")
        (field (name "MANUFACTURER PART NUMBER") "CRCW0201200KFNED")
        (field (name "TOLERANCE") "1%")
        (field (name "POWER") "50mW")
      )
      (libsource (lib "MP-LIBRARY") (part "CRCW0201200KFNED"))
    )
    (comp (ref "R859")
      (value "1M2")
      (footprint "R0201_C")
      (description "1.2 MOhms ±1% 0.05W, 1/20W Chip Resistor 0201 (0603 Metric) Thick Film")
      (fields
        (field (name "MANUFACTURER") "Vishay Dale")
        (field (name "MANUFACTURER PART NUMBER") "CRCW02011M20FNED")
        (field (name "TOLERANCE") "1%")
      )
      (libsource (lib "MP-LIBRARY") (part "CRCW02011M20FNED"))
    )
    (comp (ref "R860")
      (value "3k74")
      (footprint "R0201_C")
      (description "3.74 kOhms ±1% 0.05W, 1/20W Chip Resistor 0201 (0603 Metric) Thick Film")
      (fields
        (field (name "MANUFACTURER") "Vishay Dale")
        (field (name "MANUFACTURER PART NUMBER") "CRCW02013K74FNED")
        (field (name "TOLERANCE") "1%")
      )
      (libsource (lib "MP-LIBRARY") (part "CRCW02013K74FNED"))
    )
    (comp (ref "R861")
      (value "150k")
      (footprint "R0201_C")
      (fields
        (field (name "MANUFACTURER") "Vishay")
        (field (name "MANUFACTURER PART NUMBER") "CRCW0201150KFNED")
        (field (name "TOLERANCE") "1%")
        (field (name "POWER") "50mW")
      )
      (libsource (lib "MP-LIBRARY") (part "CRCW0201150KFNED"))
    )
    (comp (ref "TP800")
      (value "Test Point")
      (footprint "testpad_0.9mm")
      (description "Test pad, 0.90mm circular pad")
      (libsource (lib "MP-LIBRARY") (part "Test Point"))
    )
    (comp (ref "TP801")
      (value "Test Point")
      (footprint "testpad_0.9mm")
      (description "Test pad, 0.90mm circular pad")
      (libsource (lib "MP-LIBRARY") (part "Test Point"))
    )
    (comp (ref "TP802")
      (value "Test Point")
      (footprint "testpad_0.9mm")
      (description "Test pad, 0.90mm circular pad")
      (libsource (lib "MP-LIBRARY") (part "Test Point"))
    )
    (comp (ref "TP803")
      (value "Test Point")
      (footprint "testpad_0.9mm")
      (description "Test pad, 0.90mm circular pad")
      (libsource (lib "MP-LIBRARY") (part "Test Point"))
    )
    (comp (ref "TP804")
      (value "Test Point")
      (footprint "testpad_0.9mm")
      (description "Test pad, 0.90mm circular pad")
      (libsource (lib "MP-LIBRARY") (part "Test Point"))
    )
    (comp (ref "TP805")
      (value "Test Point")
      (footprint "testpad_0.9mm")
      (description "Test pad, 0.90mm circular pad")
      (libsource (lib "MP-LIBRARY") (part "Test Point"))
    )
    (comp (ref "U800")
      (value "AD8233ACBZ-R7")
      (footprint "AD8233ACBZ-R7")
      (description "Analog front end, ECG, RLD amp, BGA-20")
      (fields (field (name "MANUFACTURER") "Analog Devices"))
      (libsource (lib "MP-LIBRARY") (part "AD8233ACBZ-R7"))
    )
    (comp (ref "U801")
      (value "AD8232ACPZ-R7")
      (footprint "FP-CP-20-8-IPC_C")
      (description "Analog Circuit, 1 Func, 1 Channel")
      (fields
        (field (name "SUPPLIER PART NUMBER") "584-AD8232ACPZ-R7")
        (field (name "MANUFACTURER") "Analog Devices")
      )
      (libsource (lib "MP-LIBRARY") (part "AD8232ACPZ-R7"))
    )
    (comp (ref "U802")
      (value "AD8233ACBZ-R7")
      (footprint "AD8233ACBZ-R7")
      (description "Analog front end, ECG, RLD amp, BGA-20")
      (fields (field (name "MANUFACTURER") "Analog Devices"))
      (libsource (lib "MP-LIBRARY") (part "AD8233ACBZ-R7"))
    )
    (comp (ref "U803")
      (value "AD8232ACPZ-R7")
      (footprint "FP-CP-20-8-IPC_C")
      (description "Analog Circuit, 1 Func, 1 Channel")
      (fields
        (field (name "SUPPLIER PART NUMBER") "584-AD8232ACPZ-R7")
        (field (name "MANUFACTURER") "Analog Devices")
      )
      (libsource (lib "MP-LIBRARY") (part "AD8232ACPZ-R7"))
    )
  )
  (nets
    (net (code "3") (name "/ECG.HR_LOD") (class "Default")
      (node (ref "U800") (pin "C1") (pinfunction "LOD_C1") (pintype "output"))
    )
    (net (code "4") (name "/ECG.HR_OUT") (class "Default")
      (node (ref "C806") (pin "1") (pinfunction "1_1") (pintype "passive"))
      (node (ref "R814") (pin "2") (pinfunction "2_2") (pintype "passive"))
      (node (ref "U800") (pin "D1") (pinfunction "OUT_D1") (pintype "output"))
    )
    (net (code "5") (name "/ECG.HR_SDNn") (class "Default")
      (node (ref "TP800") (pin "1") (pinfunction "1_1") (pintype "passive"))
      (node (ref "U800") (pin "B1") (pinfunction "~{SDN}_B1") (pintype "input"))
    )
    (net (code "6") (name "/ECG.RLD") (class "Default")
      (node (ref "TP802") (pin "1") (pinfunction "1_1") (pintype "passive"))
      (node (ref "TP803") (pin "1") (pinfunction "1_1") (pintype "passive"))
      (node (ref "U800") (pin "C2") (pinfunction "RLD_~{SDN}_C2") (pintype "input"))
      (node (ref "U802") (pin "C2") (pinfunction "RLD_~{SDN}_C2") (pintype "input"))
    )
    (net (code "7") (name "/ECG.RR_LOD") (class "Default")
      (node (ref "U802") (pin "C1") (pinfunction "LOD_C1") (pintype "output"))
    )
    (net (code "8") (name "/ECG.RR_OUT") (class "Default")
      (node (ref "C820") (pin "1") (pinfunction "1_1") (pintype "passive"))
      (node (ref "R844") (pin "2") (pinfunction "2_2") (pintype "passive"))
      (node (ref "U802") (pin "D1") (pinfunction "OUT_D1") (pintype "output"))
    )
    (net (code "9") (name "/ECG.RR_SDNn") (class "Default")
      (node (ref "TP801") (pin "1") (pinfunction "1_1") (pintype "passive"))
      (node (ref "U802") (pin "B1") (pinfunction "~{SDN}_B1") (pintype "input"))
    )
    (net (code "10") (name "/ECG_HR+") (class "Default")
      (node (ref "R805") (pin "1") (pinfunction "1_1") (pintype "passive"))
      (node (ref "R808") (pin "1") (pinfunction "1_1") (pintype "passive"))
    )
    (net (code "11") (name "/ECG_HR-") (class "Default")
      (node (ref "R807") (pin "1") (pinfunction "1_1") (pintype "passive"))
      (node (ref "R809") (pin "1") (pinfunction "1_1") (pintype "passive"))
    )
    (net (code "12") (name "/ECG_HR_IOUT") (class "Default")
      (node (ref "R801") (pin "1") (pinfunction "1_1") (pintype "passive"))
      (node (ref "R811") (pin "1") (pinfunction "1_1") (pintype "passive"))
      (node (ref "U800") (pin "B4") (pinfunction "IAOUT_B4") (pintype "output"))
    )
    (net (code "13") (name "/ECG_HR_REFOUT") (class "Default")
      (node (ref "C804") (pin "1") (pinfunction "1_1") (pintype "passive"))
      (node (ref "C805") (pin "1") (pinfunction "1_1") (pintype "passive"))
      (node (ref "R813") (pin "1") (pinfunction "1_1") (pintype "passive"))
      (node (ref "U800") (pin "C3") (pinfunction "REFOUT_C3") (pintype "output"))
    )
    (net (code "14") (name "/ECG_HR_SW") (class "Default")
      (node (ref "C804") (pin "2") (pinfunction "2_2") (pintype "passive"))
      (node (ref "R802") (pin "1") (pinfunction "1_1") (pintype "passive"))
      (node (ref "U800") (pin "D4") (pinfunction "SW_D4") (pintype "passive"))
    )
    (net (code "15") (name "/ECG_RR+") (class "Default")
      (node (ref "R837") (pin "1") (pinfunction "1_1") (pintype "passive"))
      (node (ref "R839") (pin "1") (pinfunction "1_1") (pintype "passive"))
    )
    (net (code "16") (name "/ECG_RR-") (class "Default")
      (node (ref "R836") (pin "1") (pinfunction "1_1") (pintype "passive"))
      (node (ref "R840") (pin "1") (pinfunction "1_1") (pintype "passive"))
    )
    (net (code "17") (name "/ECG_RR_IOUT") (class "Default")
      (node (ref "R830") (pin "2") (pinfunction "2_2") (pintype "passive"))
      (node (ref "R842") (pin "1") (pinfunction "1_1") (pintype "passive"))
      (node (ref "U802") (pin "B4") (pinfunction "IAOUT_B4") (pintype "output"))
    )
    (net (code "18") (name "/ECG_RR_REFOUT") (class "Default")
      (node (ref "C818") (pin "2") (pinfunction "2_2") (pintype "passive"))
      (node (ref "C819") (pin "1") (pinfunction "1_1") (pintype "passive"))
      (node (ref "R845") (pin "1") (pinfunction "1_1") (pintype "passive"))
      (node (ref "U802") (pin "C3") (pinfunction "REFOUT_C3") (pintype "output"))
    )
    (net (code "19") (name "/ECG_RR_SW") (class "Default")
      (node (ref "C818") (pin "1") (pinfunction "1_1") (pintype "passive"))
      (node (ref "R832") (pin "2") (pinfunction "2_2") (pintype "passive"))
      (node (ref "U802") (pin "D4") (pinfunction "SW_D4") (pintype "passive"))
    )
    (net (code "20") (name "/EMG1+") (class "Default")
      (node (ref "R820") (pin "1") (pinfunction "1_1") (pintype "passive"))
      (node (ref "R824") (pin "1") (pinfunction "1_1") (pintype "passive"))
    )
    (net (code "21") (name "/EMG1-") (class "Default")
      (node (ref "R822") (pin "1") (pinfunction "1_1") (pintype "passive"))
      (node (ref "R823") (pin "1") (pinfunction "1_1") (pintype "passive"))
    )
    (net (code "22") (name "/EMG1.LOD") (class "Default")
      (node (ref "U801") (pin "12") (pinfunction "LOD+_12") (pintype "output"))
    )
    (net (code "23") (name "/EMG1.OUT") (class "Default")
      (node (ref "C813") (pin "2") (pinfunction "2_2") (pintype "passive"))
      (node (ref "R838") (pin "1") (pinfunction "1_1") (pintype "passive"))
      (node (ref "U801") (pin "10") (pinfunction "OUT_10") (pintype "output"))
    )
    (net (code "24") (name "/EMG1.SDNn") (class "Default")
      (node (ref "TP805") (pin "1") (pinfunction "1_1") (pintype "passive"))
      (node (ref "U801") (pin "13") (pinfunction "~{SDN}_13") (pintype "input"))
    )
    (net (code "25") (name "/EMG1_HPDRIVE") (class "Default")
      (node (ref "C812") (pin "1") (pinfunction "1_1") (pintype "passive"))
      (node (ref "U801") (pin "1") (pinfunction "HPDRIVE_1") (pintype "output"))
    )
    (net (code "26") (name "/EMG1_HPSENSE") (class "Default")
      (node (ref "C812") (pin "2") (pinfunction "2_2") (pintype "passive"))
      (node (ref "R826") (pin "1") (pinfunction "1_1") (pintype "passive"))
      (node (ref "U801") (pin "20") (pinfunction "HPSENSE_20") (pintype "input"))
    )
    (net (code "27") (name "/EMG1_IN+") (class "Default")
      (node (ref "D810") (pin "2") (pinfunction "A_2") (pintype "passive"))
      (node (ref "D814") (pin "1") (pinfunction "K_1") (pintype "passive"))
      (node (ref "R820") (pin "2") (pinfunction "2_2") (pintype "passive"))
      (node (ref "U801") (pin "2") (pinfunction "+IN_2") (pintype "tri_state"))
    )
    (net (code "28") (name "/EMG1_IN-") (class "Default")
      (node (ref "D811") (pin "2") (pinfunction "A_2") (pintype "passive"))
      (node (ref "D815") (pin "1") (pinfunction "K_1") (pintype "passive"))
      (node (ref "R822") (pin "2") (pinfunction "2_2") (pintype "passive"))
      (node (ref "U801") (pin "3") (pinfunction "-IN_3") (pintype "tri_state"))
    )
    (net (code "29") (name "/EMG1_IOUT") (class "Default")
      (node (ref "C809") (pin "2") (pinfunction "2_2") (pintype "passive"))
      (node (ref "R817") (pin "2") (pinfunction "2_2") (pintype "passive"))
      (node (ref "U801") (pin "19") (pinfunction "IAOUT_19") (pintype "passive"))
    )
    (net (code "30") (name "/EMG1_OPAMP+") (class "Default")
      (node (ref "C829") (pin "2") (pinfunction "2_2") (pintype "passive"))
      (node (ref "R828") (pin "2") (pinfunction "2_2") (pintype "passive"))
      (node (ref "U801") (pin "7") (pinfunction "OPAMP+_7") (pintype "tri_state"))
    )
    (net (code "31") (name "/EMG1_OPAMP-") (class "Default")
      (node (ref "R829") (pin "2") (pinfunction "2_2") (pintype "passive"))
      (node (ref "R838") (pin "2") (pinfunction "2_2") (pintype "passive"))
      (node (ref "U801") (pin "9") (pinfunction "OPAMP-_9") (pintype "tri_state"))
    )
    (net (code "32") (name "/EMG1_REFIN") (class "Default")
      (node (ref "C807") (pin "2") (pinfunction "2_2") (pintype "passive"))
      (node (ref "R815") (pin "2") (pinfunction "2_2") (pintype "passive"))
      (node (ref "R819") (pin "1") (pinfunction "1_1") (pintype "passive"))
      (node (ref "U801") (pin "18") (pinfunction "REFIN_18") (pintype "input"))
    )
    (net (code "33") (name "/EMG1_REFOUT") (class "Default")
      (node (ref "C811") (pin "1") (pinfunction "1_1") (pintype "passive"))
      (node (ref "C829") (pin "1") (pinfunction "1_1") (pintype "passive"))
      (node (ref "R816") (pin "1") (pinfunction "1_1") (pintype "passive"))
      (node (ref "R829") (pin "1") (pinfunction "1_1") (pintype "passive"))
      (node (ref "U801") (pin "8") (pinfunction "REFOUT_8") (pintype "passive"))
    )
    (net (code "34") (name "/EMG1_RLD") (class "Default")
      (node (ref "C810") (pin "1") (pinfunction "1_1") (pintype "passive"))
      (node (ref "R825") (pin "2") (pinfunction "2_2") (pintype "passive"))
      (node (ref "U801") (pin "5") (pinfunction "RLD_5") (pintype "passive"))
    )
    (net (code "35") (name "/EMG1_RLDFB") (class "Default")
      (node (ref "C810") (pin "2") (pinfunction "2_2") (pintype "passive"))
      (node (ref "U801") (pin "4") (pinfunction "RLDFB_4") (pintype "passive"))
    )
    (net (code "36") (name "/EMG1_SW") (class "Default")
      (node (ref "C811") (pin "2") (pinfunction "2_2") (pintype "passive"))
      (node (ref "R818") (pin "1") (pinfunction "1_1") (pintype "passive"))
      (node (ref "U801") (pin "6") (pinfunction "SW_6") (pintype "passive"))
    )
    (net (code "37") (name "/EMG1_VO1") (class "Default")
      (node (ref "C809") (pin "1") (pinfunction "1_1") (pintype "passive"))
      (node (ref "R816") (pin "2") (pinfunction "2_2") (pintype "passive"))
      (node (ref "R827") (pin "1") (pinfunction "1_1") (pintype "passive"))
    )
    (net (code "38") (name "/EMG2+") (class "Default")
      (node (ref "R849") (pin "1") (pinfunction "1_1") (pintype "passive"))
      (node (ref "R850") (pin "1") (pinfunction "1_1") (pintype "passive"))
    )
    (net (code "39") (name "/EMG2-") (class "Default")
      (node (ref "R848") (pin "1") (pinfunction "1_1") (pintype "passive"))
      (node (ref "R851") (pin "1") (pinfunction "1_1") (pintype "passive"))
    )
    (net (code "40") (name "/EMG2.LOD") (class "Default")
      (node (ref "U803") (pin "12") (pinfunction "LOD+_12") (pintype "output"))
    )
    (net (code "41") (name "/EMG2.OUT") (class "Default")
      (node (ref "C828") (pin "2") (pinfunction "2_2") (pintype "passive"))
      (node (ref "R861") (pin "1") (pinfunction "1_1") (pintype "passive"))
      (node (ref "U803") (pin "10") (pinfunction "OUT_10") (pintype "output"))
    )
    (net (code "42") (name "/EMG2.SDNn") (class "Default")
      (node (ref "TP804") (pin "1") (pinfunction "1_1") (pintype "passive"))
      (node (ref "U803") (pin "13") (pinfunction "~{SDN}_13") (pintype "input"))
    )
    (net (code "43") (name "/EMG2_HPDRIVE") (class "Default")
      (node (ref "C824") (pin "1") (pinfunction "1_1") (pintype "passive"))
      (node (ref "U803") (pin "1") (pinfunction "HPDRIVE_1") (pintype "output"))
    )
    (net (code "44") (name "/EMG2_HPSENSE") (class "Default")
      (node (ref "C824") (pin "2") (pinfunction "2_2") (pintype "passive"))
      (node (ref "R853") (pin "1") (pinfunction "1_1") (pintype "passive"))
      (node (ref "U803") (pin "20") (pinfunction "HPSENSE_20") (pintype "input"))
    )
    (net (code "45") (name "/EMG2_IN+") (class "Default")
      (node (ref "D808") (pin "2") (pinfunction "A_2") (pintype "passive"))
      (node (ref "D812") (pin "1") (pinfunction "K_1") (pintype "passive"))
      (node (ref "R850") (pin "2") (pinfunction "2_2") (pintype "passive"))
      (node (ref "U803") (pin "2") (pinfunction "+IN_2") (pintype "tri_state"))
    )
    (net (code "46") (name "/EMG2_IN-") (class "Default")
      (node (ref "D809") (pin "2") (pinfunction "A_2") (pintype "passive"))
      (node (ref "D813") (pin "1") (pinfunction "K_1") (pintype "passive"))
      (node (ref "R851") (pin "2") (pinfunction "2_2") (pintype "passive"))
      (node (ref "U803") (pin "3") (pinfunction "-IN_3") (pintype "tri_state"))
    )
    (net (code "47") (name "/EMG2_IOUT") (class "Default")
      (node (ref "C827") (pin "2") (pinfunction "2_2") (pintype "passive"))
      (node (ref "R854") (pin "2") (pinfunction "2_2") (pintype "passive"))
      (node (ref "U803") (pin "19") (pinfunction "IAOUT_19") (pintype "passive"))
    )
    (net (code "48") (name "/EMG2_OPAMP+") (class "Default")
      (node (ref "C826") (pin "2") (pinfunction "2_2") (pintype "passive"))
      (node (ref "R860") (pin "2") (pinfunction "2_2") (pintype "passive"))
      (node (ref "U803") (pin "7") (pinfunction "OPAMP+_7") (pintype "tri_state"))
    )
    (net (code "49") (name "/EMG2_OPAMP-") (class "Default")
      (node (ref "R856") (pin "2") (pinfunction "2_2") (pintype "passive"))
      (node (ref "R861") (pin "2") (pinfunction "2_2") (pintype "passive"))
      (node (ref "U803") (pin "9") (pinfunction "OPAMP-_9") (pintype "tri_state"))
    )
    (net (code "50") (name "/EMG2_REFIN") (class "Default")
      (node (ref "C822") (pin "1") (pinfunction "1_1") (pintype "passive"))
      (node (ref "R846") (pin "1") (pinfunction "1_1") (pintype "passive"))
      (node (ref "R847") (pin "2") (pinfunction "2_2") (pintype "passive"))
      (node (ref "U803") (pin "18") (pinfunction "REFIN_18") (pintype "input"))
    )
    (net (code "51") (name "/EMG2_REFOUT") (class "Default")
      (node (ref "C825") (pin "2") (pinfunction "2_2") (pintype "passive"))
      (node (ref "C826") (pin "1") (pinfunction "1_1") (pintype "passive"))
      (node (ref "R856") (pin "1") (pinfunction "1_1") (pintype "passive"))
      (node (ref "R858") (pin "1") (pinfunction "1_1") (pintype "passive"))
      (node (ref "U803") (pin "8") (pinfunction "REFOUT_8") (pintype "passive"))
    )
    (net (code "52") (name "/EMG2_RLD") (class "Default")
      (node (ref "C823") (pin "1") (pinfunction "1_1") (pintype "passive"))
      (node (ref "R852") (pin "2") (pinfunction "2_2") (pintype "passive"))
      (node (ref "U803") (pin "5") (pinfunction "RLD_5") (pintype "passive"))
    )
    (net (code "53") (name "/EMG2_RLDFB") (class "Default")
      (node (ref "C823") (pin "2") (pinfunction "2_2") (pintype "passive"))
      (node (ref "U803") (pin "4") (pinfunction "RLDFB_4") (pintype "passive"))
    )
    (net (code "54") (name "/EMG2_SW") (class "Default")
      (node (ref "C825") (pin "1") (pinfunction "1_1") (pintype "passive"))
      (node (ref "R855") (pin "1") (pinfunction "1_1") (pintype "passive"))
      (node (ref "U803") (pin "6") (pinfunction "SW_6") (pintype "passive"))
    )
    (net (code "55") (name "/EMG2_VO1") (class "Default")
      (node (ref "C827") (pin "1") (pinfunction "1_1") (pintype "passive"))
      (node (ref "R858") (pin "2") (pinfunction "2_2") (pintype "passive"))
      (node (ref "R859") (pin "1") (pinfunction "1_1") (pintype "passive"))
    )
    (net (code "58") (name "GND") (class "Default")
      (node (ref "C800") (pin "1") (pinfunction "1_1") (pintype "passive"))
      (node (ref "C801") (pin "1") (pinfunction "1_1") (pintype "passive"))
      (node (ref "C807") (pin "1") (pinfunction "1_1") (pintype "passive"))
      (node (ref "C808") (pin "1") (pinfunction "1_1") (pintype "passive"))
      (node (ref "C815") (pin "1") (pinfunction "1_1") (pintype "passive"))
      (node (ref "C816") (pin "1") (pinfunction "1_1") (pintype "passive"))
      (node (ref "C821") (pin "2") (pinfunction "2_2") (pintype "passive"))
      (node (ref "C822") (pin "2") (pinfunction "2_2") (pintype "passive"))
      (node (ref "D804") (pin "2") (pinfunction "A_2") (pintype "passive"))
      (node (ref "D805") (pin "2") (pinfunction "A_2") (pintype "passive"))
      (node (ref "D806") (pin "2") (pinfunction "A_2") (pintype "passive"))
      (node (ref "D807") (pin "2") (pinfunction "A_2") (pintype "passive"))
      (node (ref "D812") (pin "2") (pinfunction "A_2") (pintype "passive"))
      (node (ref "D813") (pin "2") (pinfunction "A_2") (pintype "passive"))
      (node (ref "D814") (pin "2") (pinfunction "A_2") (pintype "passive"))
      (node (ref "D815") (pin "2") (pinfunction "A_2") (pintype "passive"))
      (node (ref "R804") (pin "2") (pinfunction "2_2") (pintype "passive"))
      (node (ref "R819") (pin "2") (pinfunction "2_2") (pintype "passive"))
      (node (ref "R834") (pin "2") (pinfunction "2_2") (pintype "passive"))
      (node (ref "R847") (pin "1") (pinfunction "1_1") (pintype "passive"))
      (node (ref "U800") (pin "A1") (pinfunction "GND_A1") (pintype "power_in"))
      (node (ref "U801") (pin "16") (pinfunction "GND_16") (pintype "power_in"))
      (node (ref "U801") (pin "21") (pinfunction "EP_21") (pintype "power_in"))
      (node (ref "U802") (pin "A1") (pinfunction "GND_A1") (pintype "power_in"))
      (node (ref "U803") (pin "16") (pinfunction "GND_16") (pintype "power_in"))
      (node (ref "U803") (pin "21") (pinfunction "EP_21") (pintype "power_in"))
    )
    (net (code "59") (name "Net-(C806-Pad2)") (class "Default")
      (node (ref "C806") (pin "2") (pinfunction "2_2") (pintype "passive"))
      (node (ref "R811") (pin "2") (pinfunction "2_2") (pintype "passive"))
      (node (ref "R812") (pin "1") (pinfunction "1_1") (pintype "passive"))
    )
    (net (code "60") (name "Net-(C813-Pad1)") (class "Default")
      (node (ref "C813") (pin "1") (pinfunction "1_1") (pintype "passive"))
      (node (ref "R827") (pin "2") (pinfunction "2_2") (pintype "passive"))
      (node (ref "R828") (pin "1") (pinfunction "1_1") (pintype "passive"))
    )
    (net (code "61") (name "Net-(C820-Pad2)") (class "Default")
      (node (ref "C820") (pin "2") (pinfunction "2_2") (pintype "passive"))
      (node (ref "R842") (pin "2") (pinfunction "2_2") (pintype "passive"))
      (node (ref "R843") (pin "1") (pinfunction "1_1") (pintype "passive"))
    )
    (net (code "62") (name "Net-(C828-Pad1)") (class "Default")
      (node (ref "C828") (pin "1") (pinfunction "1_1") (pintype "passive"))
      (node (ref "R859") (pin "2") (pinfunction "2_2") (pintype "passive"))
      (node (ref "R860") (pin "1") (pinfunction "1_1") (pintype "passive"))
    )
    (net (code "63") (name "Net-(D800-A)") (class "Default")
      (node (ref "D800") (pin "2") (pinfunction "A_2") (pintype "passive"))
      (node (ref "D804") (pin "1") (pinfunction "K_1") (pintype "passive"))
      (node (ref "R805") (pin "2") (pinfunction "2_2") (pintype "passive"))
      (node (ref "U800") (pin "B5") (pinfunction "+IN_B5") (pintype "input"))
    )
    (net (code "64") (name "Net-(D801-A)") (class "Default")
      (node (ref "D801") (pin "2") (pinfunction "A_2") (pintype "passive"))
      (node (ref "D805") (pin "1") (pinfunction "K_1") (pintype "passive"))
      (node (ref "R807") (pin "2") (pinfunction "2_2") (pintype "passive"))
      (node (ref "U800") (pin "C5") (pinfunction "-IN_C5") (pintype "input"))
    )
    (net (code "65") (name "Net-(D802-A)") (class "Default")
      (node (ref "D802") (pin "2") (pinfunction "A_2") (pintype "passive"))
      (node (ref "D806") (pin "1") (pinfunction "K_1") (pintype "passive"))
      (node (ref "R839") (pin "2") (pinfunction "2_2") (pintype "passive"))
      (node (ref "U802") (pin "B5") (pinfunction "+IN_B5") (pintype "input"))
    )
    (net (code "66") (name "Net-(D803-A)") (class "Default")
      (node (ref "D803") (pin "2") (pinfunction "A_2") (pintype "passive"))
      (node (ref "D807") (pin "1") (pinfunction "K_1") (pintype "passive"))
      (node (ref "R840") (pin "2") (pinfunction "2_2") (pintype "passive"))
      (node (ref "U802") (pin "C5") (pinfunction "-IN_C5") (pintype "input"))
    )
    (net (code "67") (name "Net-(R801-Pad2)") (class "Default")
      (node (ref "R801") (pin "2") (pinfunction "2_2") (pintype "passive"))
      (node (ref "R802") (pin "2") (pinfunction "2_2") (pintype "passive"))
      (node (ref "R803") (pin "1") (pinfunction "1_1") (pintype "passive"))
    )
    (net (code "68") (name "Net-(R808-Pad2)") (class "Default")
      (node (ref "R808") (pin "2") (pinfunction "2_2") (pintype "passive"))
      (node (ref "R809") (pin "2") (pinfunction "2_2") (pintype "passive"))
      (node (ref "R810") (pin "1") (pinfunction "1_1") (pintype "passive"))
    )
    (net (code "69") (name "Net-(R817-Pad1)") (class "Default")
      (node (ref "R817") (pin "1") (pinfunction "1_1") (pintype "passive"))
      (node (ref "R818") (pin "2") (pinfunction "2_2") (pintype "passive"))
      (node (ref "R826") (pin "2") (pinfunction "2_2") (pintype "passive"))
    )
    (net (code "70") (name "Net-(R823-Pad2)") (class "Default")
      (node (ref "R823") (pin "2") (pinfunction "2_2") (pintype "passive"))
      (node (ref "R824") (pin "2") (pinfunction "2_2") (pintype "passive"))
      (node (ref "R825") (pin "1") (pinfunction "1_1") (pintype "passive"))
    )
    (net (code "71") (name "Net-(R830-Pad1)") (class "Default")
      (node (ref "R830") (pin "1") (pinfunction "1_1") (pintype "passive"))
      (node (ref "R831") (pin "2") (pinfunction "2_2") (pintype "passive"))
      (node (ref "R832") (pin "1") (pinfunction "1_1") (pintype "passive"))
    )
    (net (code "72") (name "Net-(R836-Pad2)") (class "Default")
      (node (ref "R836") (pin "2") (pinfunction "2_2") (pintype "passive"))
      (node (ref "R837") (pin "2") (pinfunction "2_2") (pintype "passive"))
      (node (ref "R841") (pin "1") (pinfunction "1_1") (pintype "passive"))
    )
    (net (code "73") (name "Net-(R848-Pad2)") (class "Default")
      (node (ref "R848") (pin "2") (pinfunction "2_2") (pintype "passive"))
      (node (ref "R849") (pin "2") (pinfunction "2_2") (pintype "passive"))
      (node (ref "R852") (pin "1") (pinfunction "1_1") (pintype "passive"))
    )
    (net (code "74") (name "Net-(R853-Pad2)") (class "Default")
      (node (ref "R853") (pin "2") (pinfunction "2_2") (pintype "passive"))
      (node (ref "R854") (pin "1") (pinfunction "1_1") (pintype "passive"))
      (node (ref "R855") (pin "2") (pinfunction "2_2") (pintype "passive"))
    )
    (net (code "75") (name "Net-(U800A-AC_{slash}_~{DC})") (class "Default")
      (node (ref "R806") (pin "1") (pinfunction "1_1") (pintype "passive"))
      (node (ref "U800") (pin "B2") (pinfunction "AC_/_~{DC}_B2") (pintype "input"))
    )
    (net (code "76") (name "Net-(U800A-HPDRIVE)") (class "Default")
      (node (ref "C802") (pin "1") (pinfunction "1_1") (pintype "passive"))
      (node (ref "U800") (pin "A5") (pinfunction "HPDRIVE_A5") (pintype "output"))
    )
    (net (code "77") (name "Net-(U800A-HPSENSE)") (class "Default")
      (node (ref "C802") (pin "2") (pinfunction "2_2") (pintype "passive"))
      (node (ref "R803") (pin "2") (pinfunction "2_2") (pintype "passive"))
      (node (ref "U800") (pin "A4") (pinfunction "HPSENSE_A4") (pintype "input"))
    )
    (net (code "78") (name "Net-(U800A-REFIN)") (class "Default")
      (node (ref "C800") (pin "2") (pinfunction "2_2") (pintype "passive"))
      (node (ref "R800") (pin "2") (pinfunction "2_2") (pintype "passive"))
      (node (ref "R804") (pin "1") (pinfunction "1_1") (pintype "passive"))
      (node (ref "U800") (pin "A3") (pinfunction "REFIN_A3") (pintype "input"))
    )
    (net (code "79") (name "Net-(U800A-RLD)") (class "Default")
      (node (ref "C803") (pin "1") (pinfunction "1_1") (pintype "passive"))
      (node (ref "R810") (pin "2") (pinfunction "2_2") (pintype "passive"))
      (node (ref "U800") (pin "D5") (pinfunction "RLD_D5") (pintype "output"))
    )
    (net (code "80") (name "Net-(U800A-RLDFB)") (class "Default")
      (node (ref "C803") (pin "2") (pinfunction "2_2") (pintype "passive"))
      (node (ref "U800") (pin "C4") (pinfunction "RLDFB_C4") (pintype "input"))
    )
    (net (code "81") (name "Net-(U800B-OPAMP+)") (class "Default")
      (node (ref "C805") (pin "2") (pinfunction "2_2") (pintype "passive"))
      (node (ref "R812") (pin "2") (pinfunction "2_2") (pintype "passive"))
      (node (ref "U800") (pin "D3") (pinfunction "OPAMP+_D3") (pintype "input"))
    )
    (net (code "82") (name "Net-(U800B-OPAMP-)") (class "Default")
      (node (ref "R813") (pin "2") (pinfunction "2_2") (pintype "passive"))
      (node (ref "R814") (pin "1") (pinfunction "1_1") (pintype "passive"))
      (node (ref "U800") (pin "D2") (pinfunction "OPAMP-_D2") (pintype "input"))
    )
    (net (code "83") (name "Net-(U801A-AC{slash}~{DC})") (class "Default")
      (node (ref "R821") (pin "1") (pinfunction "1_1") (pintype "passive"))
      (node (ref "U801") (pin "14") (pinfunction "AC/~{DC}_14") (pintype "input"))
    )
    (net (code "84") (name "Net-(U802A-AC_{slash}_~{DC})") (class "Default")
      (node (ref "R835") (pin "1") (pinfunction "1_1") (pintype "passive"))
      (node (ref "U802") (pin "B2") (pinfunction "AC_/_~{DC}_B2") (pintype "input"))
    )
    (net (code "85") (name "Net-(U802A-HPDRIVE)") (class "Default")
      (node (ref "C817") (pin "1") (pinfunction "1_1") (pintype "passive"))
      (node (ref "U802") (pin "A5") (pinfunction "HPDRIVE_A5") (pintype "output"))
    )
    (net (code "86") (name "Net-(U802A-HPSENSE)") (class "Default")
      (node (ref "C817") (pin "2") (pinfunction "2_2") (pintype "passive"))
      (node (ref "R831") (pin "1") (pinfunction "1_1") (pintype "passive"))
      (node (ref "U802") (pin "A4") (pinfunction "HPSENSE_A4") (pintype "input"))
    )
    (net (code "87") (name "Net-(U802A-REFIN)") (class "Default")
      (node (ref "C816") (pin "2") (pinfunction "2_2") (pintype "passive"))
      (node (ref "R833") (pin "2") (pinfunction "2_2") (pintype "passive"))
      (node (ref "R834") (pin "1") (pinfunction "1_1") (pintype "passive"))
      (node (ref "U802") (pin "A3") (pinfunction "REFIN_A3") (pintype "input"))
    )
    (net (code "88") (name "Net-(U802A-RLD)") (class "Default")
      (node (ref "C814") (pin "1") (pinfunction "1_1") (pintype "passive"))
      (node (ref "R841") (pin "2") (pinfunction "2_2") (pintype "passive"))
      (node (ref "U802") (pin "D5") (pinfunction "RLD_D5") (pintype "output"))
    )
    (net (code "89") (name "Net-(U802A-RLDFB)") (class "Default")
      (node (ref "C814") (pin "2") (pinfunction "2_2") (pintype "passive"))
      (node (ref "U802") (pin "C4") (pinfunction "RLDFB_C4") (pintype "input"))
    )
    (net (code "90") (name "Net-(U802B-OPAMP+)") (class "Default")
      (node (ref "C819") (pin "2") (pinfunction "2_2") (pintype "passive"))
      (node (ref "R843") (pin "2") (pinfunction "2_2") (pintype "passive"))
      (node (ref "U802") (pin "D3") (pinfunction "OPAMP+_D3") (pintype "input"))
    )
    (net (code "91") (name "Net-(U802B-OPAMP-)") (class "Default")
      (node (ref "R844") (pin "1") (pinfunction "1_1") (pintype "passive"))
      (node (ref "R845") (pin "2") (pinfunction "2_2") (pintype "passive"))
      (node (ref "U802") (pin "D2") (pinfunction "OPAMP-_D2") (pintype "input"))
    )
    (net (code "92") (name "Net-(U803A-AC{slash}~{DC})") (class "Default")
      (node (ref "R857") (pin "1") (pinfunction "1_1") (pintype "passive"))
      (node (ref "U803") (pin "14") (pinfunction "AC/~{DC}_14") (pintype "input"))
    )
    (net (code "93") (name "VDDA") (class "Default")
      (node (ref "C801") (pin "2") (pinfunction "2_2") (pintype "passive"))
      (node (ref "C808") (pin "2") (pinfunction "2_2") (pintype "passive"))
      (node (ref "C815") (pin "2") (pinfunction "2_2") (pintype "passive"))
      (node (ref "C821") (pin "1") (pinfunction "1_1") (pintype "passive"))
      (node (ref "D800") (pin "1") (pinfunction "K_1") (pintype "passive"))
      (node (ref "D801") (pin "1") (pinfunction "K_1") (pintype "passive"))
      (node (ref "D802") (pin "1") (pinfunction "K_1") (pintype "passive"))
      (node (ref "D803") (pin "1") (pinfunction "K_1") (pintype "passive"))
      (node (ref "D808") (pin "1") (pinfunction "K_1") (pintype "passive"))
      (node (ref "D809") (pin "1") (pinfunction "K_1") (pintype "passive"))
      (node (ref "D810") (pin "1") (pinfunction "K_1") (pintype "passive"))
      (node (ref "D811") (pin "1") (pinfunction "K_1") (pintype "passive"))
      (node (ref "R800") (pin "1") (pinfunction "1_1") (pintype "passive"))
      (node (ref "R806") (pin "2") (pinfunction "2_2") (pintype "passive"))
      (node (ref "R815") (pin "1") (pinfunction "1_1") (pintype "passive"))
      (node (ref "R821") (pin "2") (pinfunction "2_2") (pintype "passive"))
      (node (ref "R833") (pin "1") (pinfunction "1_1") (pintype "passive"))
      (node (ref "R835") (pin "2") (pinfunction "2_2") (pintype "passive"))
      (node (ref "R846") (pin "2") (pinfunction "2_2") (pintype "passive"))
      (node (ref "R857") (pin "2") (pinfunction "2_2") (pintype "passive"))
      (node (ref "U800") (pin "A2") (pinfunction "+VS_A2") (pintype "power_in"))
      (node (ref "U800") (pin "B3") (pinfunction "FR_B3") (pintype "input"))
      (node (ref "U801") (pin "15") (pinfunction "FR_15") (pintype "input"))
      (node (ref "U801") (pin "17") (pinfunction "+VS_17") (pintype "power_in"))
      (node (ref "U802") (pin "A2") (pinfunction "+VS_A2") (pintype "power_in"))
      (node (ref "U802") (pin "B3") (pinfunction "FR_B3") (pintype "input"))
      (node (ref "U803") (pin "15") (pinfunction "FR_15") (pintype "input"))
      (node (ref "U803") (pin "17") (pinfunction "+VS_17") (pintype "power_in"))
    )
    (net (code "94") (name "unconnected-(U801A-LOD--Pad11)") (class "Default")
      (node (ref "U801") (pin "11") (pinfunction "LOD-_11") (pintype "output+no_connect"))
    )
    (net (code "95") (name "unconnected-(U803A-LOD--Pad11)") (class "Default")
      (node (ref "U803") (pin "11") (pinfunction "LOD-_11") (pintype "output+no_connect"))
    )
  )
)
